# Sheet2.net
KiCad netlist of a schematic drawn in Altium Designer
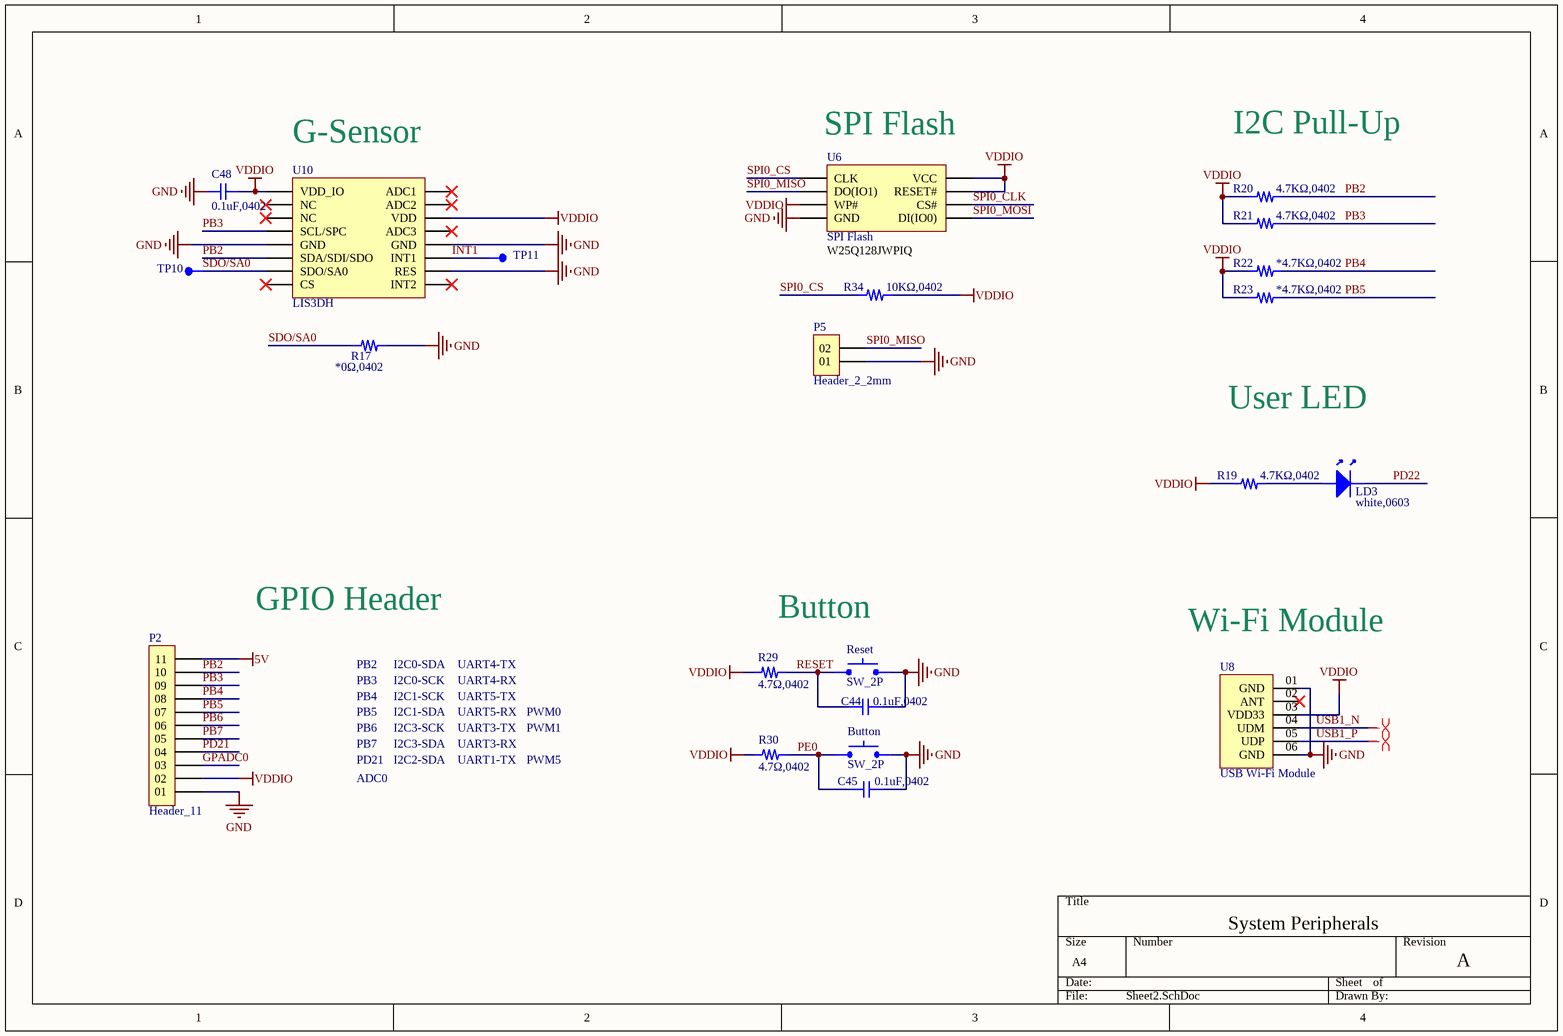
[diagram p0: Sheet2.SchDoc]

(export (version "E")
  (design (tool "Eeschema 10.0.6"))
  (components
    (comp (ref "Button") (value "SW_2P") (footprint "SW_2P_4") (libsource (lib "myLib1") (part "SW_2P")))
    (comp (ref "C44") (value "0.1uF,0402") (footprint "C0402") (libsource (lib "myLib1") (part "Cap")))
    (comp (ref "C45") (value "0.1uF,0402") (footprint "C0402") (libsource (lib "myLib1") (part "Cap")))
    (comp (ref "C48") (value "0.1uF,0402") (footprint "C0402") (libsource (lib "myLib1") (part "Cap")))
    (comp (ref "LD3")
      (value "white,0603")
      (footprint "LED0603")
      (libsource (lib "myLib1") (part "Diode - LED"))
    )
    (comp (ref "P2")
      (value "Header_11")
      (footprint "Header_11")
      (libsource (lib "myLib1") (part "Header_11"))
    )
    (comp (ref "P5")
      (value "Header_2_2mm")
      (footprint "Header_2_2mm")
      (libsource (lib "myLib1") (part "Header_2"))
    )
    (comp (ref "R17") (value "*0Ω,0402") (footprint "R0402") (libsource (lib "myLib1") (part "Res")))
    (comp (ref "R19") (value "4.7KΩ,0402") (footprint "R0402") (libsource (lib "myLib1") (part "Res")))
    (comp (ref "R20") (value "4.7KΩ,0402") (footprint "R0402") (libsource (lib "myLib1") (part "Res")))
    (comp (ref "R21") (value "4.7KΩ,0402") (footprint "R0402") (libsource (lib "myLib1") (part "Res")))
    (comp (ref "R22") (value "*4.7KΩ,0402") (footprint "R0402") (libsource (lib "myLib1") (part "Res")))
    (comp (ref "R23") (value "*4.7KΩ,0402") (footprint "R0402") (libsource (lib "myLib1") (part "Res")))
    (comp (ref "R29") (value "4.7Ω,0402") (footprint "R0402") (libsource (lib "myLib1") (part "Res")))
    (comp (ref "R30") (value "4.7Ω,0402") (footprint "R0402") (libsource (lib "myLib1") (part "Res")))
    (comp (ref "R34") (value "10KΩ,0402") (footprint "R0402") (libsource (lib "myLib1") (part "Res")))
    (comp (ref "Reset") (value "SW_2P") (footprint "SW_2P_4") (libsource (lib "myLib1") (part "SW_2P")))
    (comp (ref "TP10") (value "TP") (footprint "TP") (libsource (lib "myLib1") (part "TP")))
    (comp (ref "TP11") (value "TP") (footprint "TP") (libsource (lib "myLib1") (part "TP")))
    (comp (ref "U6") (value "SPI Flash") (footprint "WSON8") (libsource (lib "myLib1") (part "SPI Flash")))
    (comp (ref "U8")
      (value "USB Wi-Fi Module")
      (footprint "BL-M8188FU3")
      (description "BL-M8188FU3 RTL8188FTV")
      (libsource (lib "myLib1") (part "USB Wi-Fi Module"))
    )
    (comp (ref "U10") (value "LIS3DH") (footprint "LGA-16") (libsource (lib "myLib1") (part "LIS3DH")))
  )
  (nets
    (net (code "1") (name "/GPADC0") (class "Default")
      (node (ref "P2") (pin "03") (pinfunction "03_03") (pintype "passive"))
    )
    (net (code "2") (name "/INT1") (class "Default")
      (node (ref "TP11") (pin "01") (pintype "passive"))
      (node (ref "U10") (pin "11") (pinfunction "INT1_11") (pintype "passive"))
    )
    (net (code "3") (name "/PB2") (class "Default")
      (node (ref "P2") (pin "10") (pinfunction "10_10") (pintype "passive"))
      (node (ref "R20") (pin "01") (pintype "passive"))
      (node (ref "U10") (pin "06") (pinfunction "SDA/SDI/SDO_06") (pintype "passive"))
    )
    (net (code "4") (name "/PB3") (class "Default")
      (node (ref "P2") (pin "09") (pinfunction "09_09") (pintype "passive"))
      (node (ref "R21") (pin "01") (pintype "passive"))
      (node (ref "U10") (pin "04") (pinfunction "SCL/SPC_04") (pintype "passive"))
    )
    (net (code "5") (name "/PB4") (class "Default")
      (node (ref "P2") (pin "08") (pinfunction "08_08") (pintype "passive"))
      (node (ref "R22") (pin "01") (pintype "passive"))
    )
    (net (code "6") (name "/PB5") (class "Default")
      (node (ref "P2") (pin "07") (pinfunction "07_07") (pintype "passive"))
      (node (ref "R23") (pin "01") (pintype "passive"))
    )
    (net (code "7") (name "/PB6") (class "Default")
      (node (ref "P2") (pin "06") (pinfunction "06_06") (pintype "passive"))
    )
    (net (code "8") (name "/PB7") (class "Default")
      (node (ref "P2") (pin "05") (pinfunction "05_05") (pintype "passive"))
    )
    (net (code "9") (name "/PD21") (class "Default")
      (node (ref "P2") (pin "04") (pinfunction "04_04") (pintype "passive"))
    )
    (net (code "10") (name "/PD22") (class "Default") (node (ref "LD3") (pin "02") (pintype "passive")))
    (net (code "11") (name "/PE0") (class "Default")
      (node (ref "Button") (pin "01") (pintype "passive"))
      (node (ref "C45") (pin "01") (pintype "passive"))
      (node (ref "R30") (pin "02") (pintype "passive"))
    )
    (net (code "12") (name "/RESET") (class "Default")
      (node (ref "C44") (pin "01") (pintype "passive"))
      (node (ref "R29") (pin "02") (pintype "passive"))
      (node (ref "Reset") (pin "01") (pintype "passive"))
    )
    (net (code "13") (name "/SDO{slash}SA0") (class "Default")
      (node (ref "R17") (pin "01") (pintype "passive"))
      (node (ref "TP10") (pin "01") (pintype "passive"))
      (node (ref "U10") (pin "07") (pinfunction "SDO/SA0_07") (pintype "passive"))
    )
    (net (code "14") (name "/SPI0_CLK") (class "Default")
      (node (ref "U6") (pin "01") (pinfunction "CS#_01") (pintype "passive"))
    )
    (net (code "15") (name "/SPI0_CS") (class "Default")
      (node (ref "R34") (pin "01") (pintype "passive"))
      (node (ref "U6") (pin "06") (pinfunction "CLK_06") (pintype "passive"))
    )
    (net (code "16") (name "/SPI0_MISO") (class "Default")
      (node (ref "P5") (pin "02") (pinfunction "02_02") (pintype "passive"))
      (node (ref "U6") (pin "02") (pinfunction "DO(IO1)_02") (pintype "passive"))
    )
    (net (code "17") (name "/SPI0_MOSI") (class "Default")
      (node (ref "U6") (pin "05") (pinfunction "DI(IO0)_05") (pintype "passive"))
    )
    (net (code "18") (name "/USB1_N") (class "Default")
      (node (ref "U8") (pin "04") (pinfunction "UDM_04") (pintype "passive"))
    )
    (net (code "19") (name "/USB1_P") (class "Default")
      (node (ref "U8") (pin "05") (pinfunction "UDP_05") (pintype "passive"))
    )
    (net (code "20") (name "5V") (class "Default")
      (node (ref "P2") (pin "11") (pinfunction "11_11") (pintype "passive"))
    )
    (net (code "21") (name "GND") (class "Default")
      (node (ref "Button") (pin "02") (pintype "passive"))
      (node (ref "C44") (pin "02") (pintype "passive"))
      (node (ref "C45") (pin "02") (pintype "passive"))
      (node (ref "C48") (pin "02") (pintype "passive"))
      (node (ref "P2") (pin "01") (pinfunction "01_01") (pintype "passive"))
      (node (ref "P5") (pin "01") (pinfunction "01_01") (pintype "passive"))
      (node (ref "R17") (pin "02") (pintype "passive"))
      (node (ref "Reset") (pin "02") (pintype "passive"))
      (node (ref "U10") (pin "05") (pinfunction "GND_05") (pintype "passive"))
      (node (ref "U10") (pin "10") (pinfunction "RES_10") (pintype "passive"))
      (node (ref "U10") (pin "12") (pinfunction "GND_12") (pintype "passive"))
      (node (ref "U6") (pin "04") (pinfunction "GND_04") (pintype "passive"))
      (node (ref "U8") (pin "01") (pinfunction "GND_01") (pintype "passive"))
      (node (ref "U8") (pin "06") (pinfunction "GND_06") (pintype "passive"))
    )
    (net (code "22") (name "Net-(LD3-Pad01)") (class "Default")
      (node (ref "LD3") (pin "01") (pintype "passive"))
      (node (ref "R19") (pin "01") (pintype "passive"))
    )
    (net (code "23") (name "VDDIO") (class "Default")
      (node (ref "C48") (pin "01") (pintype "passive"))
      (node (ref "P2") (pin "02") (pinfunction "02_02") (pintype "passive"))
      (node (ref "R19") (pin "02") (pintype "passive"))
      (node (ref "R20") (pin "02") (pintype "passive"))
      (node (ref "R21") (pin "02") (pintype "passive"))
      (node (ref "R22") (pin "02") (pintype "passive"))
      (node (ref "R23") (pin "02") (pintype "passive"))
      (node (ref "R29") (pin "01") (pintype "passive"))
      (node (ref "R30") (pin "01") (pintype "passive"))
      (node (ref "R34") (pin "02") (pintype "passive"))
      (node (ref "U10") (pin "01") (pinfunction "VDD_IO_01") (pintype "passive"))
      (node (ref "U10") (pin "14") (pinfunction "VDD_14") (pintype "passive"))
      (node (ref "U6") (pin "03") (pinfunction "WP#_03") (pintype "passive"))
      (node (ref "U6") (pin "07") (pinfunction "RESET#_07") (pintype "passive"))
      (node (ref "U6") (pin "08") (pinfunction "VCC_08") (pintype "passive"))
      (node (ref "U8") (pin "03") (pinfunction "VDD33_03") (pintype "passive"))
    )
    (net (code "24") (name "unconnected-(U8-ANT-Pad02)") (class "Default")
      (node (ref "U8") (pin "02") (pinfunction "ANT_02") (pintype "passive+no_connect"))
    )
    (net (code "25") (name "unconnected-(U10-ADC1-Pad16)") (class "Default")
      (node (ref "U10") (pin "16") (pinfunction "ADC1_16") (pintype "passive+no_connect"))
    )
    (net (code "26") (name "unconnected-(U10-ADC2-Pad15)") (class "Default")
      (node (ref "U10") (pin "15") (pinfunction "ADC2_15") (pintype "passive+no_connect"))
    )
    (net (code "27") (name "unconnected-(U10-ADC3-Pad13)") (class "Default")
      (node (ref "U10") (pin "13") (pinfunction "ADC3_13") (pintype "passive+no_connect"))
    )
    (net (code "28") (name "unconnected-(U10-CS-Pad08)") (class "Default")
      (node (ref "U10") (pin "08") (pinfunction "CS_08") (pintype "passive+no_connect"))
    )
    (net (code "29") (name "unconnected-(U10-INT2-Pad09)") (class "Default")
      (node (ref "U10") (pin "09") (pinfunction "INT2_09") (pintype "passive+no_connect"))
    )
    (net (code "30") (name "unconnected-(U10-NC-Pad02)") (class "Default")
      (node (ref "U10") (pin "02") (pinfunction "NC_02") (pintype "passive+no_connect"))
    )
    (net (code "31") (name "unconnected-(U10-NC-Pad03)") (class "Default")
      (node (ref "U10") (pin "03") (pinfunction "NC_03") (pintype "passive+no_connect"))
    )
  )
)
